# FE.net
KiCad netlist of a schematic drawn in Altium Designer
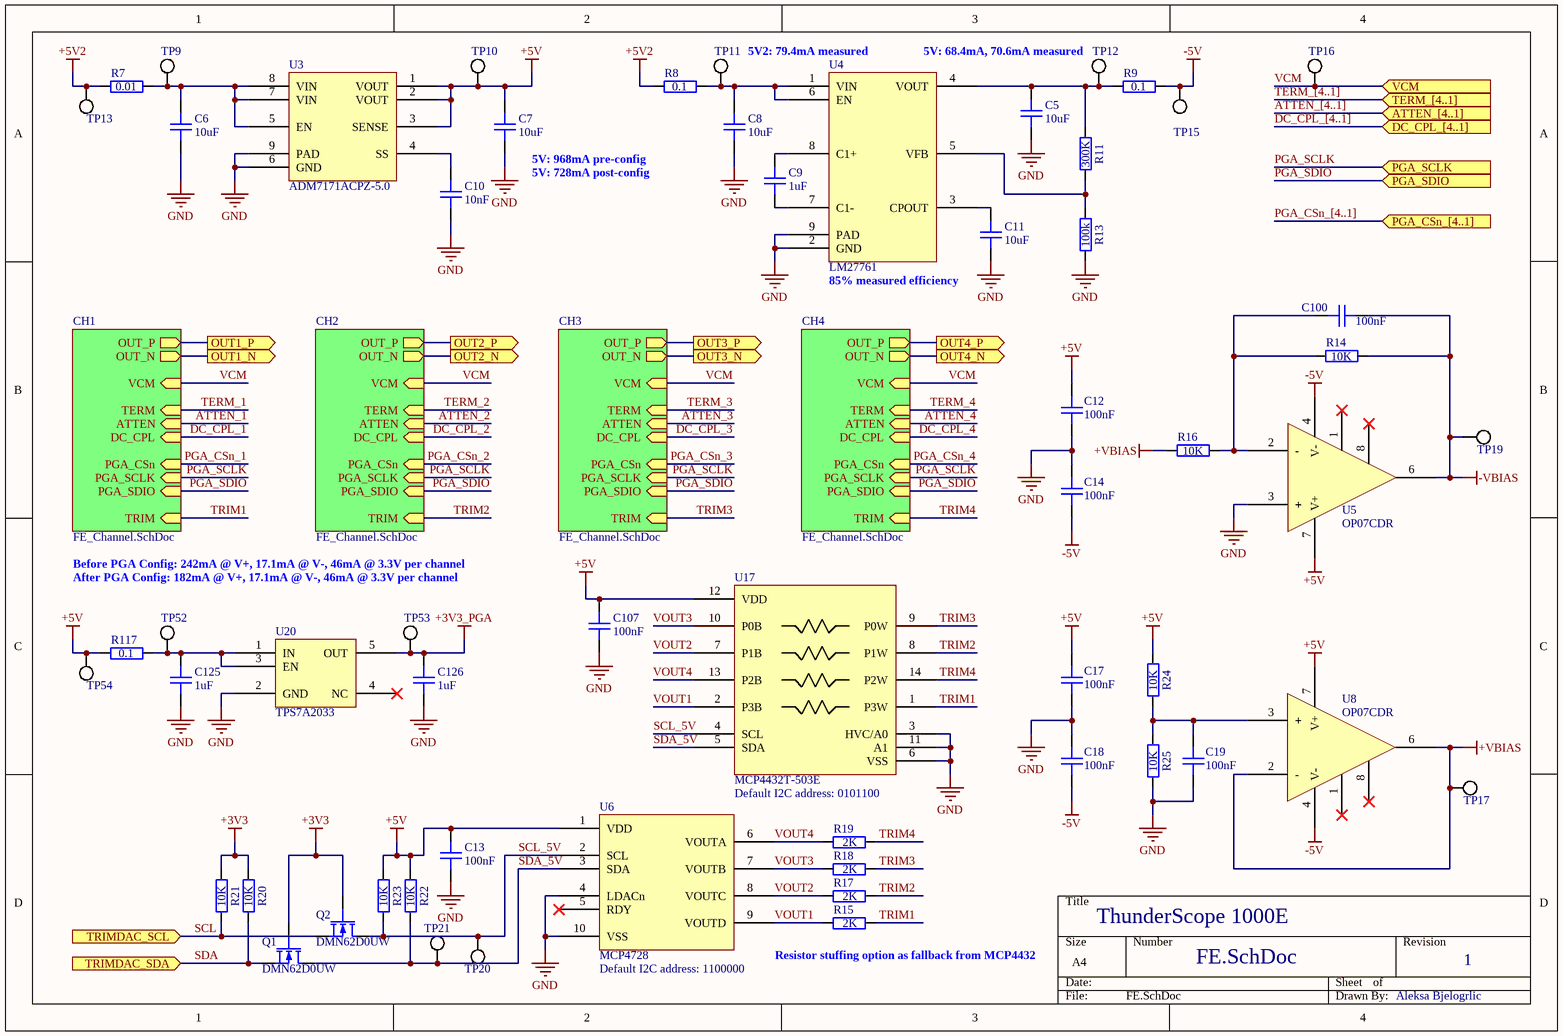
[diagram p0: FE.SchDoc]

(export (version "E")
  (design (tool "Eeschema 10.0.6"))
  (components
    (comp (ref "C5")
      (value "10uF")
      (footprint "GEN_C_0603")
      (libsource (lib "DSO") (part "CAP 10uF 10V X5R 0603"))
    )
    (comp (ref "C6")
      (value "10uF")
      (footprint "GEN_C_0603")
      (libsource (lib "DSO") (part "CAP 10uF 10V X5R 0603"))
    )
    (comp (ref "C7")
      (value "10uF")
      (footprint "GEN_C_0603")
      (libsource (lib "DSO") (part "CAP 10uF 10V X5R 0603"))
    )
    (comp (ref "C8")
      (value "10uF")
      (footprint "GEN_C_0603")
      (libsource (lib "DSO") (part "CAP 10uF 10V X5R 0603"))
    )
    (comp (ref "C9")
      (value "1uF")
      (footprint "GEN_C_0402")
      (libsource (lib "DSO") (part "CAP 1uF 25V X5R 0402"))
    )
    (comp (ref "C10")
      (value "10nF")
      (footprint "GEN_C_0402")
      (fields
        (field (name "MANUFACTURER") "Murata")
        (field (name "HOUSE PART NUMBER") "C-10nF-0402-002")
        (field (name "MANUFACTURER PART NUMBER") "GRM155R71H103KA88J")
      )
      (libsource (lib "DSO") (part "CAP 10nF 50V X7R 0402"))
    )
    (comp (ref "C11")
      (value "10uF")
      (footprint "GEN_C_0603")
      (libsource (lib "DSO") (part "CAP 10uF 10V X5R 0603"))
    )
    (comp (ref "C12")
      (value "100nF")
      (footprint "GEN_C_0402")
      (libsource (lib "DSO") (part "CAP 100nF 16V X7R 0402"))
    )
    (comp (ref "C13")
      (value "100nF")
      (footprint "GEN_C_0402")
      (libsource (lib "DSO") (part "CAP 100nF 16V X7R 0402"))
    )
    (comp (ref "C14")
      (value "100nF")
      (footprint "GEN_C_0402")
      (libsource (lib "DSO") (part "CAP 100nF 16V X7R 0402"))
    )
    (comp (ref "C17")
      (value "100nF")
      (footprint "GEN_C_0402")
      (libsource (lib "DSO") (part "CAP 100nF 16V X7R 0402"))
    )
    (comp (ref "C18")
      (value "100nF")
      (footprint "GEN_C_0402")
      (libsource (lib "DSO") (part "CAP 100nF 16V X7R 0402"))
    )
    (comp (ref "C19")
      (value "100nF")
      (footprint "GEN_C_0402")
      (libsource (lib "DSO") (part "CAP 100nF 16V X7R 0402"))
    )
    (comp (ref "C100")
      (value "100nF")
      (footprint "GEN_C_0402")
      (libsource (lib "DSO") (part "CAP 100nF 16V X7R 0402"))
    )
    (comp (ref "C107")
      (value "100nF")
      (footprint "GEN_C_0402")
      (libsource (lib "DSO") (part "CAP 100nF 16V X7R 0402"))
    )
    (comp (ref "C125")
      (value "1uF")
      (footprint "GEN_C_0402")
      (libsource (lib "DSO") (part "CAP 1uF 25V X5R 0402"))
    )
    (comp (ref "C126")
      (value "1uF")
      (footprint "GEN_C_0402")
      (libsource (lib "DSO") (part "CAP 1uF 25V X5R 0402"))
    )
    (comp (ref "Q1")
      (value "DMN62D0UW")
      (footprint "GEN_SOT_323")
      (libsource (lib "DSO") (part "NMOS DMN62D0UW"))
    )
    (comp (ref "Q2")
      (value "DMN62D0UW")
      (footprint "GEN_SOT_323")
      (libsource (lib "DSO") (part "NMOS DMN62D0UW"))
    )
    (comp (ref "R7")
      (value "0.01")
      (footprint "GEN_R_0603")
      (fields (field (name "TOLERANCE") "1%"))
      (libsource (lib "DSO") (part "RES 0.01 OHM 1% 1/4W 0603"))
    )
    (comp (ref "R8")
      (value "0.1")
      (footprint "GEN_R_0402")
      (fields (field (name "TOLERANCE") "1%"))
      (libsource (lib "DSO") (part "RES 0.1 OHM 1% 1/6W 0402"))
    )
    (comp (ref "R9")
      (value "0.1")
      (footprint "GEN_R_0402")
      (fields (field (name "TOLERANCE") "1%"))
      (libsource (lib "DSO") (part "RES 0.1 OHM 1% 1/6W 0402"))
    )
    (comp (ref "R11")
      (value "300K")
      (footprint "GEN_R_0402")
      (fields
        (field (name "TOLERANCE") "1%")
        (field (name "MANUFACTURER") "Panasonic")
        (field (name "MANUFACTURER PART NUMBER") "ERJ-2RKF3003X")
      )
      (libsource (lib "DSO") (part "RES 300K OHM 1% 1/10W 0402"))
    )
    (comp (ref "R13")
      (value "100k")
      (footprint "GEN_R_0402")
      (fields (field (name "TOLERANCE") "1%"))
      (libsource (lib "DSO") (part "RES 100K OHM 1% 1/10W 0402"))
    )
    (comp (ref "R14")
      (value "10K")
      (footprint "GEN_R_0402")
      (fields (field (name "TOLERANCE") "1%"))
      (libsource (lib "DSO") (part "RES 10K OHM 1% 1/10W 0402"))
    )
    (comp (ref "R15")
      (value "2K")
      (footprint "GEN_R_0402")
      (fields (field (name "TOLERANCE") "1%"))
      (libsource (lib "DSO") (part "RES 2K OHM 1% 1/16W 0402"))
    )
    (comp (ref "R16")
      (value "10K")
      (footprint "GEN_R_0402")
      (fields (field (name "TOLERANCE") "1%"))
      (libsource (lib "DSO") (part "RES 10K OHM 1% 1/10W 0402"))
    )
    (comp (ref "R17")
      (value "2K")
      (footprint "GEN_R_0402")
      (fields (field (name "TOLERANCE") "1%"))
      (libsource (lib "DSO") (part "RES 2K OHM 1% 1/16W 0402"))
    )
    (comp (ref "R18")
      (value "2K")
      (footprint "GEN_R_0402")
      (fields (field (name "TOLERANCE") "1%"))
      (libsource (lib "DSO") (part "RES 2K OHM 1% 1/16W 0402"))
    )
    (comp (ref "R19")
      (value "2K")
      (footprint "GEN_R_0402")
      (fields (field (name "TOLERANCE") "1%"))
      (libsource (lib "DSO") (part "RES 2K OHM 1% 1/16W 0402"))
    )
    (comp (ref "R20")
      (value "10K")
      (footprint "GEN_R_0402")
      (fields (field (name "TOLERANCE") "1%"))
      (libsource (lib "DSO") (part "RES 10K OHM 1% 1/10W 0402"))
    )
    (comp (ref "R21")
      (value "10K")
      (footprint "GEN_R_0402")
      (fields (field (name "TOLERANCE") "1%"))
      (libsource (lib "DSO") (part "RES 10K OHM 1% 1/10W 0402"))
    )
    (comp (ref "R22")
      (value "10K")
      (footprint "GEN_R_0402")
      (fields (field (name "TOLERANCE") "1%"))
      (libsource (lib "DSO") (part "RES 10K OHM 1% 1/10W 0402"))
    )
    (comp (ref "R23")
      (value "10K")
      (footprint "GEN_R_0402")
      (fields (field (name "TOLERANCE") "1%"))
      (libsource (lib "DSO") (part "RES 10K OHM 1% 1/10W 0402"))
    )
    (comp (ref "R24")
      (value "10K")
      (footprint "GEN_R_0402")
      (fields (field (name "TOLERANCE") "1%"))
      (libsource (lib "DSO") (part "RES 10K OHM 1% 1/10W 0402"))
    )
    (comp (ref "R25")
      (value "10K")
      (footprint "GEN_R_0402")
      (fields (field (name "TOLERANCE") "1%"))
      (libsource (lib "DSO") (part "RES 10K OHM 1% 1/10W 0402"))
    )
    (comp (ref "R117")
      (value "0.1")
      (footprint "GEN_R_0402")
      (fields (field (name "TOLERANCE") "1%"))
      (libsource (lib "DSO") (part "RES 0.1 OHM 1% 1/6W 0402"))
    )
    (comp (ref "TP9") (value "PCB") (footprint "GEN_TP_PCB") (libsource (lib "DSO") (part "TP PCB 1mm")))
    (comp (ref "TP10") (value "PCB") (footprint "GEN_TP_PCB") (libsource (lib "DSO") (part "TP PCB 1mm")))
    (comp (ref "TP11") (value "PCB") (footprint "GEN_TP_PCB") (libsource (lib "DSO") (part "TP PCB 1mm")))
    (comp (ref "TP12") (value "PCB") (footprint "GEN_TP_PCB") (libsource (lib "DSO") (part "TP PCB 1mm")))
    (comp (ref "TP13") (value "PCB") (footprint "GEN_TP_PCB") (libsource (lib "DSO") (part "TP PCB 1mm")))
    (comp (ref "TP15") (value "PCB") (footprint "GEN_TP_PCB") (libsource (lib "DSO") (part "TP PCB 1mm")))
    (comp (ref "TP16") (value "PCB") (footprint "GEN_TP_PCB") (libsource (lib "DSO") (part "TP PCB 1mm")))
    (comp (ref "TP17") (value "PCB") (footprint "GEN_TP_PCB") (libsource (lib "DSO") (part "TP PCB 1mm")))
    (comp (ref "TP19") (value "PCB") (footprint "GEN_TP_PCB") (libsource (lib "DSO") (part "TP PCB 1mm")))
    (comp (ref "TP20") (value "PCB") (footprint "GEN_TP_PCB") (libsource (lib "DSO") (part "TP PCB 1mm")))
    (comp (ref "TP21") (value "PCB") (footprint "GEN_TP_PCB") (libsource (lib "DSO") (part "TP PCB 1mm")))
    (comp (ref "TP52") (value "PCB") (footprint "GEN_TP_PCB") (libsource (lib "DSO") (part "TP PCB 1mm")))
    (comp (ref "TP53") (value "PCB") (footprint "GEN_TP_PCB") (libsource (lib "DSO") (part "TP PCB 1mm")))
    (comp (ref "TP54") (value "PCB") (footprint "GEN_TP_PCB") (libsource (lib "DSO") (part "TP PCB 1mm")))
    (comp (ref "U3")
      (value "ADM7171ACPZ-5.0")
      (footprint "AD_DFN8_CP-8-21")
      (libsource (lib "DSO") (part "IC LDO ADM7171ACPZ-5.0"))
    )
    (comp (ref "U4")
      (value "LM27761")
      (footprint "TI_WSON8_DSG0008A")
      (libsource (lib "DSO") (part "IC CPUMP LM27761"))
    )
    (comp (ref "U5")
      (value "OP07CDR")
      (footprint "TI_SOIC8_D0008A")
      (libsource (lib "DSO") (part "IC OPAMP OP07CDR"))
    )
    (comp (ref "U6")
      (value "MCP4728")
      (footprint "MC_MSOP10_UN")
      (libsource (lib "DSO") (part "IC DAC QUAD MCP4728"))
    )
    (comp (ref "U8")
      (value "OP07CDR")
      (footprint "TI_SOIC8_D0008A")
      (libsource (lib "DSO") (part "IC OPAMP OP07CDR"))
    )
    (comp (ref "U17")
      (value "MCP4432T-503E")
      (footprint "MC_TSSOP14")
      (libsource (lib "DSO") (part "IC DIGIPOT QUAD MCP4432T-503E"))
    )
    (comp (ref "U20")
      (value "TPS7A2033")
      (footprint "GEN_SOT23_5_950_2900X1600X1450")
      (fields
        (field (name "MANUFACTURER") "Texas Instruments")
        (field (name "MANUFACTURER PART NUMBER") "TPS7A2033PDBVR")
      )
      (libsource (lib "DSO") (part "IC LDO TPS7A2033"))
    )
  )
  (nets
    (net (code "1") (name "+3V3") (class "Default")
      (node (ref "Q1") (pin "2") (pinfunction "G_2") (pintype "passive"))
      (node (ref "Q2") (pin "2") (pinfunction "G_2") (pintype "passive"))
      (node (ref "R20") (pin "2") (pinfunction "2_2") (pintype "passive"))
      (node (ref "R21") (pin "2") (pinfunction "2_2") (pintype "passive"))
    )
    (net (code "2") (name "+3V3_PGA") (class "Default")
      (node (ref "C126") (pin "2") (pinfunction "2_2") (pintype "passive"))
      (node (ref "TP53") (pin "1") (pinfunction "1_1") (pintype "passive"))
      (node (ref "U20") (pin "5") (pinfunction "OUT_5") (pintype "power_in"))
    )
    (net (code "3") (name "+5V") (class "Default")
      (node (ref "C107") (pin "2") (pinfunction "2_2") (pintype "passive"))
      (node (ref "C12") (pin "1") (pinfunction "1_1") (pintype "passive"))
      (node (ref "C13") (pin "2") (pinfunction "2_2") (pintype "passive"))
      (node (ref "C17") (pin "1") (pinfunction "1_1") (pintype "passive"))
      (node (ref "C7") (pin "2") (pinfunction "2_2") (pintype "passive"))
      (node (ref "R117") (pin "1") (pinfunction "1_1") (pintype "passive"))
      (node (ref "R22") (pin "2") (pinfunction "2_2") (pintype "passive"))
      (node (ref "R23") (pin "2") (pinfunction "2_2") (pintype "passive"))
      (node (ref "R24") (pin "2") (pinfunction "2_2") (pintype "passive"))
      (node (ref "TP10") (pin "1") (pinfunction "1_1") (pintype "passive"))
      (node (ref "TP54") (pin "1") (pinfunction "1_1") (pintype "passive"))
      (node (ref "U17") (pin "12") (pinfunction "VDD_12") (pintype "power_in"))
      (node (ref "U3") (pin "1") (pinfunction "VOUT_1") (pintype "power_in"))
      (node (ref "U3") (pin "2") (pinfunction "VOUT_2") (pintype "power_in"))
      (node (ref "U3") (pin "3") (pinfunction "SENSE_3") (pintype "passive"))
      (node (ref "U5") (pin "7") (pinfunction "V+_7") (pintype "passive"))
      (node (ref "U6") (pin "1") (pinfunction "VDD_1") (pintype "power_in"))
      (node (ref "U8") (pin "7") (pinfunction "V+_7") (pintype "passive"))
    )
    (net (code "4") (name "+5V2") (class "Default")
      (node (ref "R7") (pin "1") (pinfunction "1_1") (pintype "passive"))
      (node (ref "R8") (pin "1") (pinfunction "1_1") (pintype "passive"))
      (node (ref "TP13") (pin "1") (pinfunction "1_1") (pintype "passive"))
    )
    (net (code "5") (name "+VBIAS") (class "Default")
      (node (ref "R16") (pin "1") (pinfunction "1_1") (pintype "passive"))
      (node (ref "TP17") (pin "1") (pinfunction "1_1") (pintype "passive"))
      (node (ref "U8") (pin "2") (pinfunction "-_2") (pintype "passive"))
      (node (ref "U8") (pin "6") (pinfunction "OUT_6") (pintype "passive"))
    )
    (net (code "6") (name "-5V") (class "Default")
      (node (ref "C14") (pin "2") (pinfunction "2_2") (pintype "passive"))
      (node (ref "C18") (pin "2") (pinfunction "2_2") (pintype "passive"))
      (node (ref "R9") (pin "2") (pinfunction "2_2") (pintype "passive"))
      (node (ref "TP15") (pin "1") (pinfunction "1_1") (pintype "passive"))
      (node (ref "U5") (pin "4") (pinfunction "V-_4") (pintype "passive"))
      (node (ref "U8") (pin "4") (pinfunction "V-_4") (pintype "passive"))
    )
    (net (code "7") (name "-VBIAS") (class "Default")
      (node (ref "C100") (pin "1") (pinfunction "1_1") (pintype "passive"))
      (node (ref "R14") (pin "2") (pinfunction "2_2") (pintype "passive"))
      (node (ref "TP19") (pin "1") (pinfunction "1_1") (pintype "passive"))
      (node (ref "U5") (pin "6") (pinfunction "OUT_6") (pintype "passive"))
    )
    (net (code "33") (name "/SCL") (class "Default")
      (node (ref "Q2") (pin "3") (pinfunction "S_3") (pintype "passive"))
      (node (ref "R21") (pin "1") (pinfunction "1_1") (pintype "passive"))
    )
    (net (code "34") (name "/SCL_5V") (class "Default")
      (node (ref "Q2") (pin "1") (pinfunction "D_1") (pintype "passive"))
      (node (ref "R23") (pin "1") (pinfunction "1_1") (pintype "passive"))
      (node (ref "TP20") (pin "1") (pinfunction "1_1") (pintype "passive"))
      (node (ref "U17") (pin "4") (pinfunction "SCL_4") (pintype "passive"))
      (node (ref "U6") (pin "2") (pinfunction "SCL_2") (pintype "passive"))
    )
    (net (code "35") (name "/SDA") (class "Default")
      (node (ref "Q1") (pin "3") (pinfunction "S_3") (pintype "passive"))
      (node (ref "R20") (pin "1") (pinfunction "1_1") (pintype "passive"))
    )
    (net (code "36") (name "/SDA_5V") (class "Default")
      (node (ref "Q1") (pin "1") (pinfunction "D_1") (pintype "passive"))
      (node (ref "R22") (pin "1") (pinfunction "1_1") (pintype "passive"))
      (node (ref "TP21") (pin "1") (pinfunction "1_1") (pintype "passive"))
      (node (ref "U17") (pin "5") (pinfunction "SDA_5") (pintype "passive"))
      (node (ref "U6") (pin "3") (pinfunction "SDA_3") (pintype "passive"))
    )
    (net (code "42") (name "/TRIM1") (class "Default")
      (node (ref "R15") (pin "1") (pinfunction "1_1") (pintype "passive"))
      (node (ref "U17") (pin "1") (pinfunction "P3W_1") (pintype "passive"))
    )
    (net (code "43") (name "/TRIM2") (class "Default")
      (node (ref "R17") (pin "1") (pinfunction "1_1") (pintype "passive"))
      (node (ref "U17") (pin "8") (pinfunction "P1W_8") (pintype "passive"))
    )
    (net (code "44") (name "/TRIM3") (class "Default")
      (node (ref "R18") (pin "1") (pinfunction "1_1") (pintype "passive"))
      (node (ref "U17") (pin "9") (pinfunction "P0W_9") (pintype "passive"))
    )
    (net (code "45") (name "/TRIM4") (class "Default")
      (node (ref "R19") (pin "1") (pinfunction "1_1") (pintype "passive"))
      (node (ref "U17") (pin "14") (pinfunction "P2W_14") (pintype "passive"))
    )
    (net (code "46") (name "/VCM") (class "Default")
      (node (ref "TP16") (pin "1") (pinfunction "1_1") (pintype "passive"))
    )
    (net (code "47") (name "/VOUT1") (class "Default")
      (node (ref "R15") (pin "2") (pinfunction "2_2") (pintype "passive"))
      (node (ref "U17") (pin "2") (pinfunction "P3B_2") (pintype "passive"))
      (node (ref "U6") (pin "9") (pinfunction "VOUTD_9") (pintype "passive"))
    )
    (net (code "48") (name "/VOUT2") (class "Default")
      (node (ref "R17") (pin "2") (pinfunction "2_2") (pintype "passive"))
      (node (ref "U17") (pin "7") (pinfunction "P1B_7") (pintype "passive"))
      (node (ref "U6") (pin "8") (pinfunction "VOUTC_8") (pintype "passive"))
    )
    (net (code "49") (name "/VOUT3") (class "Default")
      (node (ref "R18") (pin "2") (pinfunction "2_2") (pintype "passive"))
      (node (ref "U17") (pin "10") (pinfunction "P0B_10") (pintype "passive"))
      (node (ref "U6") (pin "7") (pinfunction "VOUTB_7") (pintype "passive"))
    )
    (net (code "50") (name "/VOUT4") (class "Default")
      (node (ref "R19") (pin "2") (pinfunction "2_2") (pintype "passive"))
      (node (ref "U17") (pin "13") (pinfunction "P2B_13") (pintype "passive"))
      (node (ref "U6") (pin "6") (pinfunction "VOUTA_6") (pintype "passive"))
    )
    (net (code "51") (name "GND") (class "Default")
      (node (ref "C10") (pin "1") (pinfunction "1_1") (pintype "passive"))
      (node (ref "C107") (pin "1") (pinfunction "1_1") (pintype "passive"))
      (node (ref "C11") (pin "1") (pinfunction "1_1") (pintype "passive"))
      (node (ref "C12") (pin "2") (pinfunction "2_2") (pintype "passive"))
      (node (ref "C125") (pin "1") (pinfunction "1_1") (pintype "passive"))
      (node (ref "C126") (pin "1") (pinfunction "1_1") (pintype "passive"))
      (node (ref "C13") (pin "1") (pinfunction "1_1") (pintype "passive"))
      (node (ref "C14") (pin "1") (pinfunction "1_1") (pintype "passive"))
      (node (ref "C17") (pin "2") (pinfunction "2_2") (pintype "passive"))
      (node (ref "C18") (pin "1") (pinfunction "1_1") (pintype "passive"))
      (node (ref "C19") (pin "1") (pinfunction "1_1") (pintype "passive"))
      (node (ref "C5") (pin "1") (pinfunction "1_1") (pintype "passive"))
      (node (ref "C6") (pin "1") (pinfunction "1_1") (pintype "passive"))
      (node (ref "C7") (pin "1") (pinfunction "1_1") (pintype "passive"))
      (node (ref "C8") (pin "1") (pinfunction "1_1") (pintype "passive"))
      (node (ref "R13") (pin "1") (pinfunction "1_1") (pintype "passive"))
      (node (ref "R25") (pin "1") (pinfunction "1_1") (pintype "passive"))
      (node (ref "U17") (pin "11") (pinfunction "A1_11") (pintype "passive"))
      (node (ref "U17") (pin "3") (pinfunction "HVC/A0_3") (pintype "passive"))
      (node (ref "U17") (pin "6") (pinfunction "VSS_6") (pintype "power_in"))
      (node (ref "U20") (pin "2") (pinfunction "GND_2") (pintype "power_in"))
      (node (ref "U3") (pin "6") (pinfunction "GND_6") (pintype "power_in"))
      (node (ref "U3") (pin "9") (pinfunction "PAD_9") (pintype "passive"))
      (node (ref "U4") (pin "2") (pinfunction "GND_2") (pintype "power_in"))
      (node (ref "U4") (pin "9") (pinfunction "PAD_9") (pintype "power_in"))
      (node (ref "U5") (pin "3") (pinfunction "+_3") (pintype "passive"))
      (node (ref "U6") (pin "10") (pinfunction "VSS_10") (pintype "power_in"))
      (node (ref "U6") (pin "4") (pinfunction "LDACn_4") (pintype "passive"))
    )
    (net (code "52") (name "Net-(U3-EN)") (class "Default")
      (node (ref "C6") (pin "2") (pinfunction "2_2") (pintype "passive"))
      (node (ref "R7") (pin "2") (pinfunction "2_2") (pintype "passive"))
      (node (ref "TP9") (pin "1") (pinfunction "1_1") (pintype "passive"))
      (node (ref "U3") (pin "5") (pinfunction "EN_5") (pintype "passive"))
      (node (ref "U3") (pin "7") (pinfunction "VIN_7") (pintype "power_in"))
      (node (ref "U3") (pin "8") (pinfunction "VIN_8") (pintype "power_in"))
    )
    (net (code "53") (name "Net-(U3-SS)") (class "Default")
      (node (ref "C10") (pin "2") (pinfunction "2_2") (pintype "passive"))
      (node (ref "U3") (pin "4") (pinfunction "SS_4") (pintype "passive"))
    )
    (net (code "54") (name "Net-(U4-C1+)") (class "Default")
      (node (ref "C9") (pin "2") (pinfunction "2_2") (pintype "passive"))
      (node (ref "U4") (pin "8") (pinfunction "C1+_8") (pintype "passive"))
    )
    (net (code "55") (name "Net-(U4-C1-)") (class "Default")
      (node (ref "C9") (pin "1") (pinfunction "1_1") (pintype "passive"))
      (node (ref "U4") (pin "7") (pinfunction "C1-_7") (pintype "passive"))
    )
    (net (code "56") (name "Net-(U4-CPOUT)") (class "Default")
      (node (ref "C11") (pin "2") (pinfunction "2_2") (pintype "passive"))
      (node (ref "U4") (pin "3") (pinfunction "CPOUT_3") (pintype "passive"))
    )
    (net (code "57") (name "Net-(U4-EN)") (class "Default")
      (node (ref "C8") (pin "2") (pinfunction "2_2") (pintype "passive"))
      (node (ref "R8") (pin "2") (pinfunction "2_2") (pintype "passive"))
      (node (ref "TP11") (pin "1") (pinfunction "1_1") (pintype "passive"))
      (node (ref "U4") (pin "1") (pinfunction "VIN_1") (pintype "power_in"))
      (node (ref "U4") (pin "6") (pinfunction "EN_6") (pintype "passive"))
    )
    (net (code "58") (name "Net-(U4-VFB)") (class "Default")
      (node (ref "R11") (pin "1") (pinfunction "1_1") (pintype "passive"))
      (node (ref "R13") (pin "2") (pinfunction "2_2") (pintype "passive"))
      (node (ref "U4") (pin "5") (pinfunction "VFB_5") (pintype "passive"))
    )
    (net (code "59") (name "Net-(U4-VOUT)") (class "Default")
      (node (ref "C5") (pin "2") (pinfunction "2_2") (pintype "passive"))
      (node (ref "R11") (pin "2") (pinfunction "2_2") (pintype "passive"))
      (node (ref "R9") (pin "1") (pinfunction "1_1") (pintype "passive"))
      (node (ref "TP12") (pin "1") (pinfunction "1_1") (pintype "passive"))
      (node (ref "U4") (pin "4") (pinfunction "VOUT_4") (pintype "power_in"))
    )
    (net (code "60") (name "Net-(U5--)") (class "Default")
      (node (ref "C100") (pin "2") (pinfunction "2_2") (pintype "passive"))
      (node (ref "R14") (pin "1") (pinfunction "1_1") (pintype "passive"))
      (node (ref "R16") (pin "2") (pinfunction "2_2") (pintype "passive"))
      (node (ref "U5") (pin "2") (pinfunction "-_2") (pintype "passive"))
    )
    (net (code "61") (name "Net-(U8-+)") (class "Default")
      (node (ref "C19") (pin "2") (pinfunction "2_2") (pintype "passive"))
      (node (ref "R24") (pin "1") (pinfunction "1_1") (pintype "passive"))
      (node (ref "R25") (pin "2") (pinfunction "2_2") (pintype "passive"))
      (node (ref "U8") (pin "3") (pinfunction "+_3") (pintype "passive"))
    )
    (net (code "62") (name "Net-(U20-EN)") (class "Default")
      (node (ref "C125") (pin "2") (pinfunction "2_2") (pintype "passive"))
      (node (ref "R117") (pin "2") (pinfunction "2_2") (pintype "passive"))
      (node (ref "TP52") (pin "1") (pinfunction "1_1") (pintype "passive"))
      (node (ref "U20") (pin "1") (pinfunction "IN_1") (pintype "power_in"))
      (node (ref "U20") (pin "3") (pinfunction "EN_3") (pintype "passive"))
    )
    (net (code "63") (name "unconnected-(U5-N1-Pad1)") (class "Default")
      (node (ref "U5") (pin "1") (pinfunction "N1_1") (pintype "passive+no_connect"))
    )
    (net (code "64") (name "unconnected-(U5-N2-Pad8)") (class "Default")
      (node (ref "U5") (pin "8") (pinfunction "N2_8") (pintype "passive+no_connect"))
    )
    (net (code "65") (name "unconnected-(U6-RDY-Pad5)") (class "Default")
      (node (ref "U6") (pin "5") (pinfunction "RDY_5") (pintype "passive+no_connect"))
    )
    (net (code "66") (name "unconnected-(U8-N1-Pad1)") (class "Default")
      (node (ref "U8") (pin "1") (pinfunction "N1_1") (pintype "passive+no_connect"))
    )
    (net (code "67") (name "unconnected-(U8-N2-Pad8)") (class "Default")
      (node (ref "U8") (pin "8") (pinfunction "N2_8") (pintype "passive+no_connect"))
    )
    (net (code "68") (name "unconnected-(U20-NC-Pad4)") (class "Default")
      (node (ref "U20") (pin "4") (pinfunction "NC_4") (pintype "passive+no_connect"))
    )
  )
)
